# S4V_Motor_Driver_Board_V1_0_Schematic.net
KiCad netlist of a schematic drawn in Altium Designer
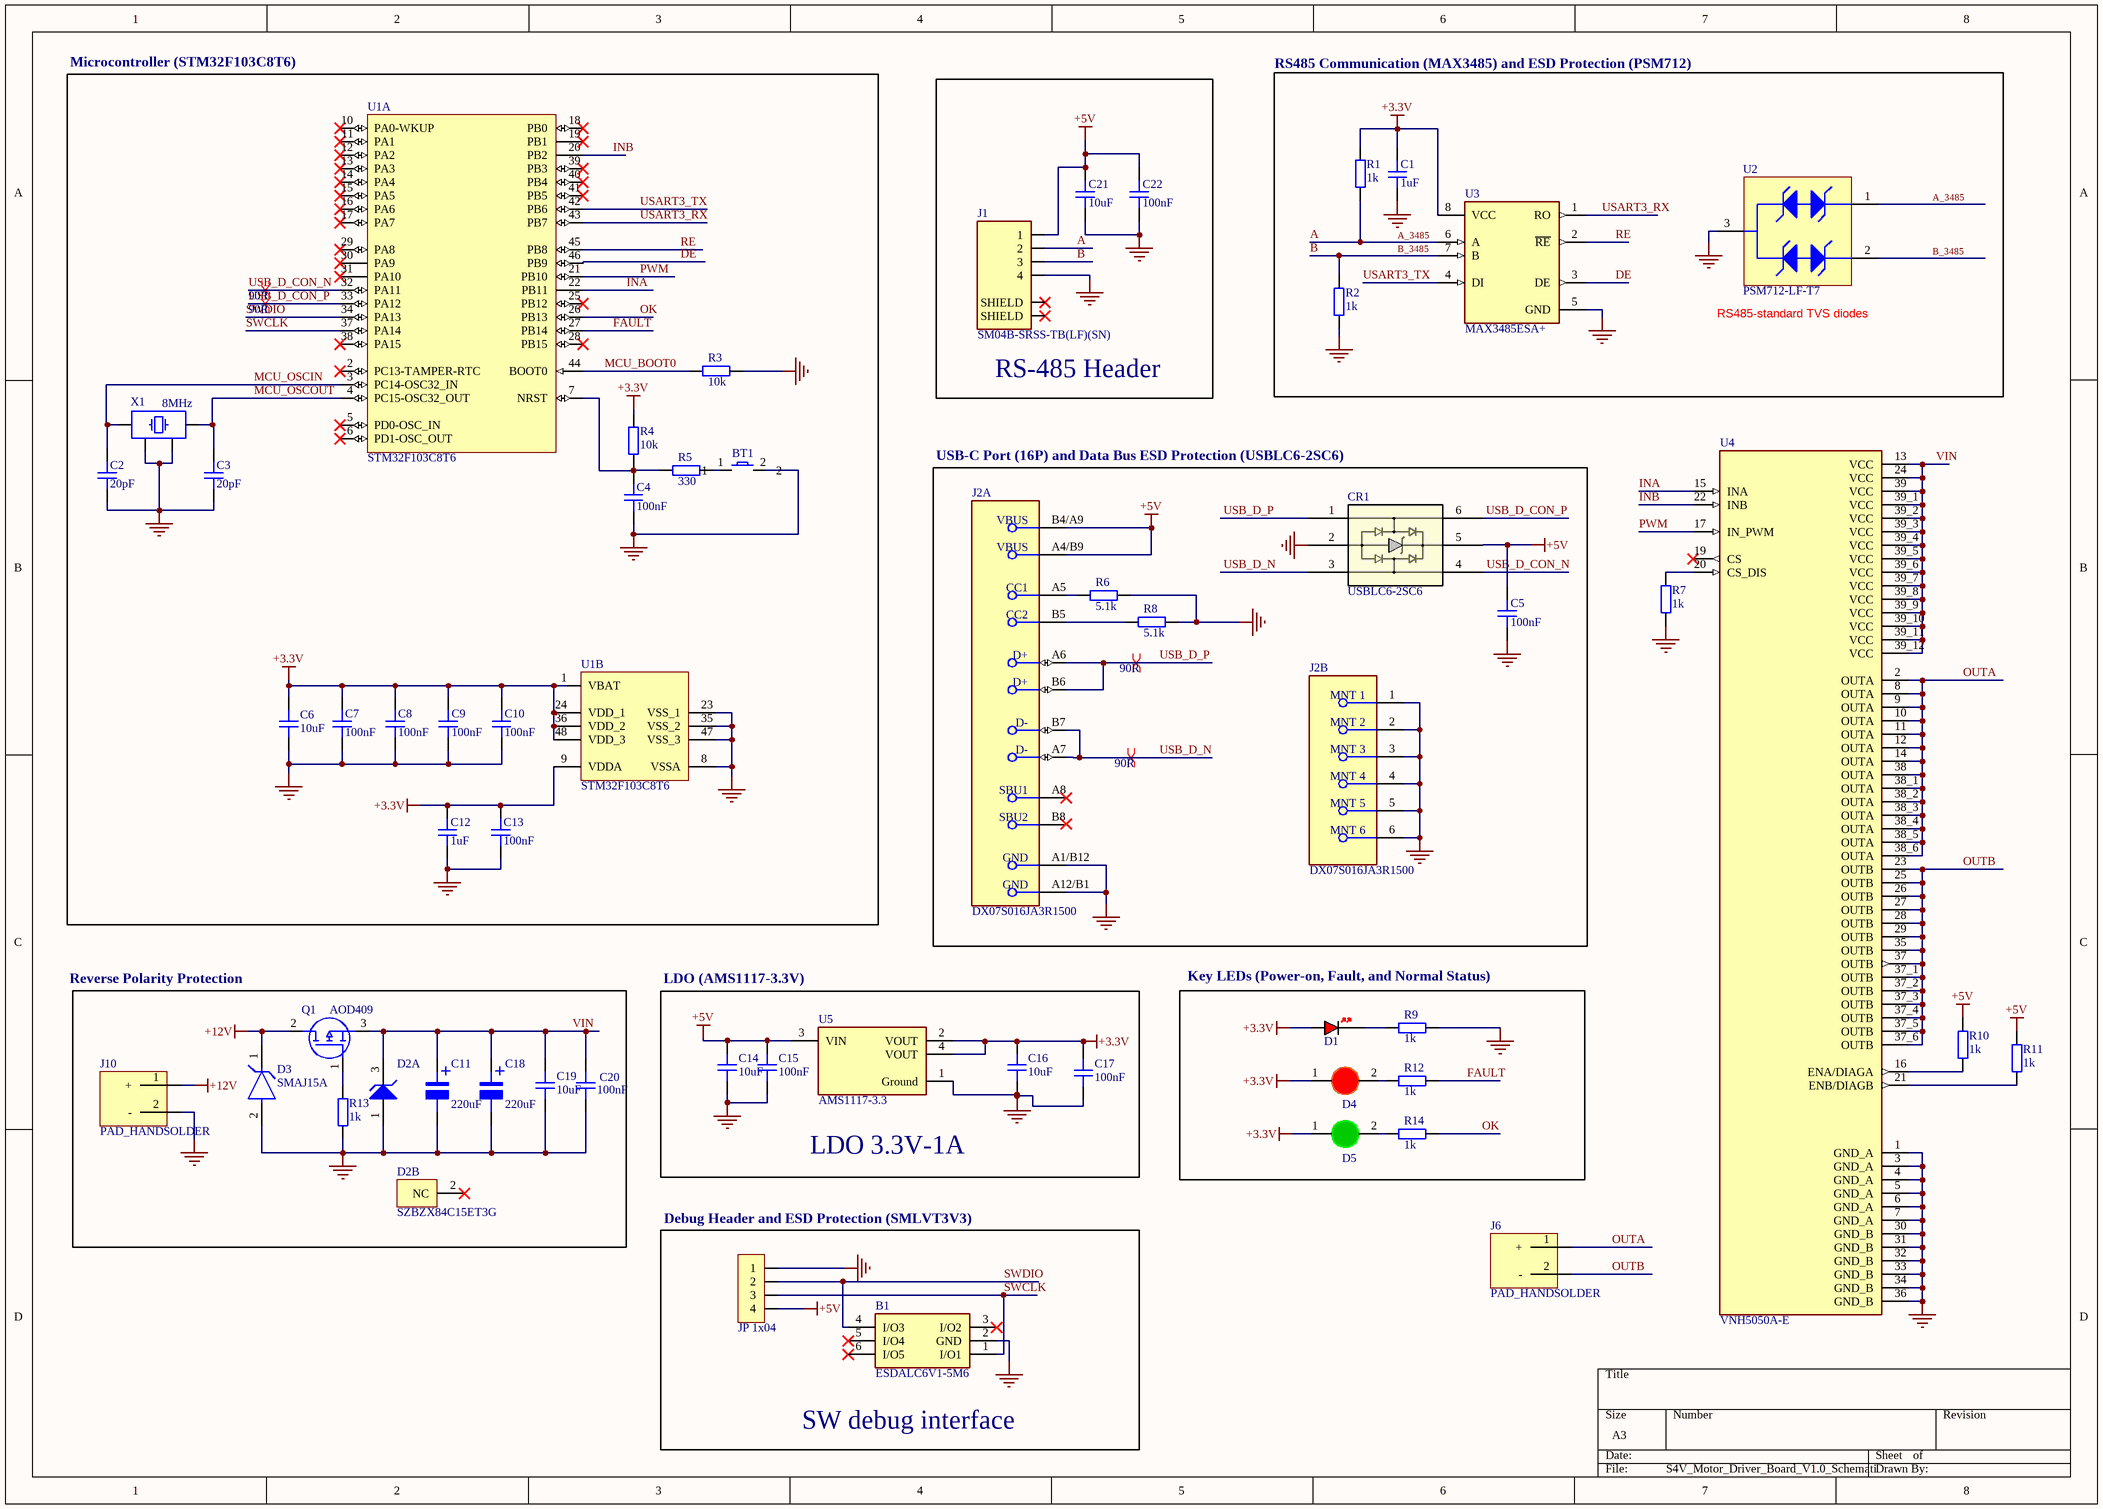
[diagram p0: S4V_Motor_Driver_Board_V1.0_Schematic.SchDoc]

(export (version "E")
  (design (tool "Eeschema 10.0.6"))
  (components
    (comp (ref "B1")
      (value "ESDALC6V1-5M6")
      (footprint "ESDALC6V15M6")
      (description "STMicroelectronics ESDALC6V1-5M6 Quint Uni-Directional TVS Diode, 30W peak, 6-Pin uQFN")
      (fields (field (name "MOUSER PART NUMBER") "511-ESDALC6V1-5M6"))
      (libsource (lib "ESDALC6V1-5M6_new") (part "ESDALC6V1-5M6"))
    )
    (comp (ref "BT1")
      (value "Button_3x4mm_SMD")
      (footprint "SMD_3x4mm_Button_PCBLib:Button_3x4mm_SMD")
      (description "Button SMD 3x4mm 2 Pins")
      (libsource (lib "SMD_3x4mm_Button_SchLib") (part "Button_3x4mm_SMD"))
    )
    (comp (ref "C1")
      (value "1uF")
      (footprint "CAP_0603")
      (description "Capacitor SMD 0603")
      (libsource (lib "Schematic-Lib-PhilsLab") (part "CAP_0603"))
    )
    (comp (ref "C2")
      (value "20pF")
      (footprint "CAP_0603")
      (description "Capacitor SMD 0603")
      (libsource (lib "Schematic-Lib-PhilsLab") (part "CAP_0603"))
    )
    (comp (ref "C3")
      (value "20pF")
      (footprint "CAP_0603")
      (description "Capacitor SMD 0603")
      (libsource (lib "Schematic-Lib-PhilsLab") (part "CAP_0603"))
    )
    (comp (ref "C4")
      (value "100nF")
      (footprint "CAP_0603")
      (description "Capacitor SMD 0603")
      (libsource (lib "Schematic-Lib-PhilsLab") (part "CAP_0603"))
    )
    (comp (ref "C5")
      (value "100nF")
      (footprint "CAP_0603")
      (description "Capacitor SMD 0603")
      (libsource (lib "Schematic-Lib-PhilsLab") (part "CAP_0603"))
    )
    (comp (ref "C6")
      (value "10uF")
      (footprint "CAP_0603")
      (description "Capacitor SMD 0603")
      (libsource (lib "Schematic-Lib-PhilsLab") (part "CAP_0603"))
    )
    (comp (ref "C7")
      (value "100nF")
      (footprint "CAP_0603")
      (description "Capacitor SMD 0603")
      (libsource (lib "Schematic-Lib-PhilsLab") (part "CAP_0603"))
    )
    (comp (ref "C8")
      (value "100nF")
      (footprint "CAP_0603")
      (description "Capacitor SMD 0603")
      (libsource (lib "Schematic-Lib-PhilsLab") (part "CAP_0603"))
    )
    (comp (ref "C9")
      (value "100nF")
      (footprint "CAP_0603")
      (description "Capacitor SMD 0603")
      (libsource (lib "Schematic-Lib-PhilsLab") (part "CAP_0603"))
    )
    (comp (ref "C10")
      (value "100nF")
      (footprint "CAP_0603")
      (description "Capacitor SMD 0603")
      (libsource (lib "Schematic-Lib-PhilsLab") (part "CAP_0603"))
    )
    (comp (ref "C11")
      (value "220uF")
      (footprint "tu nhom 8 (f)")
      (description "Dán")
      (libsource (lib "Altium_Lib_by_KhueNguyenCreator") (part "Tu Nhom 220uF 25V"))
    )
    (comp (ref "C12")
      (value "1uF")
      (footprint "CAP_0603")
      (description "Capacitor SMD 0603")
      (libsource (lib "Schematic-Lib-PhilsLab") (part "CAP_0603"))
    )
    (comp (ref "C13")
      (value "100nF")
      (footprint "CAP_0603")
      (description "Capacitor SMD 0603")
      (libsource (lib "Schematic-Lib-PhilsLab") (part "CAP_0603"))
    )
    (comp (ref "C14")
      (value "10uF")
      (footprint "CAP_0805")
      (description "Capacitor SMD 0805")
      (libsource (lib "Schematic-Lib-PhilsLab") (part "CAP_0805"))
    )
    (comp (ref "C15")
      (value "100nF")
      (footprint "CAP_0805")
      (description "Capacitor SMD 0805")
      (libsource (lib "Schematic-Lib-PhilsLab") (part "CAP_0805"))
    )
    (comp (ref "C16")
      (value "10uF")
      (footprint "CAP_0805")
      (description "Capacitor SMD 0805")
      (libsource (lib "Schematic-Lib-PhilsLab") (part "CAP_0805"))
    )
    (comp (ref "C17")
      (value "100nF")
      (footprint "CAP_0805")
      (description "Capacitor SMD 0805")
      (libsource (lib "Schematic-Lib-PhilsLab") (part "CAP_0805"))
    )
    (comp (ref "C18")
      (value "220uF")
      (footprint "tu nhom 8 (f)")
      (description "Dán")
      (libsource (lib "Altium_Lib_by_KhueNguyenCreator") (part "Tu Nhom 220uF 25V"))
    )
    (comp (ref "C19")
      (value "10uF")
      (footprint "CAP_0805")
      (description "Capacitor SMD 0805")
      (libsource (lib "Schematic-Lib-PhilsLab") (part "CAP_0805"))
    )
    (comp (ref "C20")
      (value "100nF")
      (footprint "CAP_0805")
      (description "Capacitor SMD 0805")
      (libsource (lib "Schematic-Lib-PhilsLab") (part "CAP_0805"))
    )
    (comp (ref "C21")
      (value "10uF")
      (footprint "CAP_0603")
      (description "Capacitor SMD 0603")
      (libsource (lib "Schematic-Lib-PhilsLab") (part "CAP_0603"))
    )
    (comp (ref "C22")
      (value "100nF")
      (footprint "CAP_0603")
      (description "Capacitor SMD 0603")
      (libsource (lib "Schematic-Lib-PhilsLab") (part "CAP_0603"))
    )
    (comp (ref "CR1")
      (value "USBLC6-2SC6")
      (footprint "SOT23-6L_STM")
      (description "ESD Protection for USB 2.0 High Speed")
      (fields (field (name "COPYRIGHT") "Copyright (C) 2025 Ultra Librarian. All rights reserved."))
      (libsource (lib "USBLC6-2SC6") (part "USBLC6-2SC6"))
    )
    (comp (ref "D1")
      (value "RED")
      (footprint "LED_0603_RED")
      (description "LED 0603 RED SMD")
      (libsource (lib "Schematic-Lib-PhilsLab") (part "LED_0603_RED"))
    )
    (comp (ref "D2")
      (value "SZBZX84C15ET3G")
      (footprint "ONSC-SOT-23-3-318-08_V")
      (description "Zener Voltage Regulator, 225 mW, 3-Pin SOT-23, Pb-Free, Tape and Reel")
      (fields (field (name "MANUFACTURER") "On Semiconductor"))
      (libsource (lib "Altium Content Vault") (part "ONSC-A1K3-3"))
    )
    (comp (ref "D3")
      (value "SMAJ15A")
      (footprint "FP-SMA-MFG")
      (description "24.4V Clamp 16.4A Ipp Tvs Diode Surface Mount SMA (DO-214AC)")
      (fields (field (name "OCTOPART") "https://octopart.com/smaj15a-bourns-12809353"))
      (libsource (lib "Altium Content Vault") (part "f813f71cba58e380607f5dd3caf9714"))
    )
    (comp (ref "D4")
      (value "LED 3mm")
      (footprint "LED-3MM-RED")
      (description "Cắm")
      (libsource (lib "Altium_Lib_by_KhueNguyenCreator") (part "LED 3mm Do"))
    )
    (comp (ref "D5")
      (value "LED 3mm")
      (footprint "LED-3MM-GREEN")
      (description "Cắm")
      (libsource (lib "Altium_Lib_by_KhueNguyenCreator") (part "LED 3mm Xanh La"))
    )
    (comp (ref "J1")
      (value "SM04B-SRSS-TB(LF)(SN)")
      (footprint "JST_SM04B-SRSS-TB(LF)(SN)")
      (description "Connector Header Surface Mount, Right Angle 4 position 0.039 (1.00mm)")
      (fields (field (name "MF") "JST Sales"))
      (libsource (lib "SM04B-SRSS-TB_LF__SN_") (part "SM04B-SRSS-TB(LF)(SN)"))
    )
    (comp (ref "J2")
      (value "DX07S016JA3R1500")
      (footprint "FP-DX07S016JA3R1500-MFG")
      (description "CONN RCP USB2.0 TYP C 24P SMD RA")
      (libsource (lib "Altium Content Vault") (part "86c7019cab7ffbad937e454fd6d8a8a"))
    )
    (comp (ref "J6")
      (value "PAD_HANDSOLDER")
      (footprint "PCBComponent_1")
      (description "HandSolder Pad for PWR IN")
      (libsource (lib "HandSolderPadPWR") (part "PAD_HANDSOLDER"))
    )
    (comp (ref "J10")
      (value "PAD_HANDSOLDER")
      (footprint "PCBComponent_1")
      (description "HandSolder Pad for PWR IN")
      (libsource (lib "HandSolderPadPWR") (part "PAD_HANDSOLDER"))
    )
    (comp (ref "JP1")
      (value "JP 1x04")
      (footprint "JP 1x4 DT")
      (description "Cắm")
      (libsource (lib "Altium_Lib_by_KhueNguyenCreator") (part "JP 1x4 2.54 Duc Thang"))
    )
    (comp (ref "Q1")
      (value "AOD409")
      (footprint "AOD409")
      (description "60V P-Channel MOSFET")
      (libsource (lib "AOD409") (part "AOD409"))
    )
    (comp (ref "R1")
      (value "1k")
      (footprint "RES_0603")
      (description "Resistor SMD 0603")
      (libsource (lib "Schematic-Lib-PhilsLab") (part "RES_0603"))
    )
    (comp (ref "R2")
      (value "1k")
      (footprint "RES_0603")
      (description "Resistor SMD 0603")
      (libsource (lib "Schematic-Lib-PhilsLab") (part "RES_0603"))
    )
    (comp (ref "R3")
      (value "10k")
      (footprint "RES_0603")
      (description "Resistor SMD 0603")
      (libsource (lib "Schematic-Lib-PhilsLab") (part "RES_0603"))
    )
    (comp (ref "R4")
      (value "10k")
      (footprint "RES_0603")
      (description "Resistor SMD 0603")
      (libsource (lib "Schematic-Lib-PhilsLab") (part "RES_0603"))
    )
    (comp (ref "R5")
      (value "330")
      (footprint "RES_0603")
      (description "Resistor SMD 0603")
      (libsource (lib "Schematic-Lib-PhilsLab") (part "RES_0603"))
    )
    (comp (ref "R6")
      (value "5.1k")
      (footprint "RES_0603")
      (description "Resistor SMD 0603")
      (libsource (lib "Schematic-Lib-PhilsLab") (part "RES_0603"))
    )
    (comp (ref "R7")
      (value "1k")
      (footprint "RES_0402")
      (description "Resistor SMD 0402")
      (libsource (lib "Schematic-Lib-PhilsLab") (part "RES_0402"))
    )
    (comp (ref "R8")
      (value "5.1k")
      (footprint "RES_0603")
      (description "Resistor SMD 0603")
      (libsource (lib "Schematic-Lib-PhilsLab") (part "RES_0603"))
    )
    (comp (ref "R9")
      (value "1k")
      (footprint "RES_0603")
      (description "Resistor SMD 0603")
      (libsource (lib "Schematic-Lib-PhilsLab") (part "RES_0603"))
    )
    (comp (ref "R10")
      (value "1k")
      (footprint "RES_0402")
      (description "Resistor SMD 0402")
      (libsource (lib "Schematic-Lib-PhilsLab") (part "RES_0402"))
    )
    (comp (ref "R11")
      (value "1k")
      (footprint "RES_0402")
      (description "Resistor SMD 0402")
      (libsource (lib "Schematic-Lib-PhilsLab") (part "RES_0402"))
    )
    (comp (ref "R12")
      (value "1k")
      (footprint "RES_0603")
      (description "Resistor SMD 0603")
      (libsource (lib "Schematic-Lib-PhilsLab") (part "RES_0603"))
    )
    (comp (ref "R13")
      (value "1k")
      (footprint "RES_0603")
      (description "Resistor SMD 0603")
      (libsource (lib "Schematic-Lib-PhilsLab") (part "RES_0603"))
    )
    (comp (ref "R14")
      (value "1k")
      (footprint "RES_0603")
      (description "Resistor SMD 0603")
      (libsource (lib "Schematic-Lib-PhilsLab") (part "RES_0603"))
    )
    (comp (ref "U1")
      (value "STM32F103C8T6")
      (footprint "STM-LQFP48_L")
      (libsource (lib "Altium Content Vault") (part "MC-ARM-STM32F103X8_B-SQ48"))
    )
    (comp (ref "U2")
      (value "PSM712-LF-T7")
      (footprint "PRKT-SOT23-3_V")
      (fields (field (name "MANUFACTURER") "Protek Devices") (field (name "VOLTAGE") "12V"))
      (libsource (lib "Altium Content Vault") (part "PRTK-PSM712-SOT23-3"))
    )
    (comp (ref "U3")
      (value "MAX3485ESA+")
      (footprint "FP-S8-5-MFG")
      (description "IC TXRX RS485/422 10MBPS 8SOIC")
      (fields
        (field (name "MANUFACTURER PART NUMBER") "MAX3485EESA+")
        (field (name "OCTOPART") "https://octopart.com/max3485eesa%2B-maxim+integrated-39731903")
      )
      (libsource (lib "Altium Content Vault") (part "be0caabdb159a9a12bcb36ec340889e"))
    )
    (comp (ref "U4")
      (value "VNH5050A-E")
      (footprint "SOP50P1030X247-39N")
      (description "- Motor Driver Power MOSFET Parallel, PWM PowerSSO-36 TP")
      (fields (field (name "MF") "STMicroelectronics"))
      (libsource (lib "VNH5050A-E") (part "VNH5050A-E"))
    )
    (comp (ref "U5")
      (value "AMS1117-3.3")
      (footprint "FP-AMS1117-IPC_C")
      (description "LDO Voltage Regulators 1A, 3.3V")
      (fields
        (field (name "OCTOPART") "https://octopart.com/ams1117-3.3-advanced+monolithic+systems-25899300")
        (field (name "MANUFACTURER") "Advanced Monolithic Systems")
      )
      (libsource (lib "Altium Content Vault") (part "8bdbb5f8e77002000e30dd2845d0354"))
    )
    (comp (ref "X1")
      (value "8MHz")
      (footprint "XTAL_3225")
      (description "Crystal SMD 24MHz 10PPM 7pF 3225")
      (fields
        (field (name "MANUFACTURER") "Epson")
        (field (name "MANUFACTURER PART NUMBER") "TSX-3225 24.0000MF15X-AC")
      )
      (libsource (lib "Schematic-Lib-PhilsLab") (part "TSX-3225_24.0000MF15X-AC"))
    )
  )
  (nets
    (net (code "1") (name "+3.3V") (class "Default")
      (node (ref "C1") (pin "2") (pinfunction "2_2") (pintype "passive"))
      (node (ref "C10") (pin "2") (pinfunction "2_2") (pintype "passive"))
      (node (ref "C12") (pin "2") (pinfunction "2_2") (pintype "passive"))
      (node (ref "C13") (pin "2") (pinfunction "2_2") (pintype "passive"))
      (node (ref "C16") (pin "2") (pinfunction "2_2") (pintype "passive"))
      (node (ref "C17") (pin "2") (pinfunction "2_2") (pintype "passive"))
      (node (ref "C6") (pin "2") (pinfunction "2_2") (pintype "passive"))
      (node (ref "C7") (pin "2") (pinfunction "2_2") (pintype "passive"))
      (node (ref "C8") (pin "2") (pinfunction "2_2") (pintype "passive"))
      (node (ref "C9") (pin "2") (pinfunction "2_2") (pintype "passive"))
      (node (ref "D1") (pin "A") (pinfunction "A_A") (pintype "passive"))
      (node (ref "D4") (pin "1") (pinfunction "A_1") (pintype "passive"))
      (node (ref "D5") (pin "1") (pinfunction "A_1") (pintype "passive"))
      (node (ref "R1") (pin "1") (pinfunction "1_1") (pintype "passive"))
      (node (ref "R4") (pin "2") (pinfunction "2_2") (pintype "passive"))
      (node (ref "U1") (pin "1") (pinfunction "VBAT_1") (pintype "power_in"))
      (node (ref "U1") (pin "24") (pinfunction "VDD_1_24") (pintype "power_in"))
      (node (ref "U1") (pin "36") (pinfunction "VDD_2_36") (pintype "power_in"))
      (node (ref "U1") (pin "48") (pinfunction "VDD_3_48") (pintype "power_in"))
      (node (ref "U1") (pin "9") (pinfunction "VDDA_9") (pintype "power_in"))
      (node (ref "U3") (pin "8") (pinfunction "VCC_8") (pintype "power_in"))
      (node (ref "U5") (pin "2") (pinfunction "VOUT_2") (pintype "passive"))
      (node (ref "U5") (pin "4") (pinfunction "VOUT_4") (pintype "passive"))
    )
    (net (code "2") (name "+5V") (class "Default")
      (node (ref "C14") (pin "2") (pinfunction "2_2") (pintype "passive"))
      (node (ref "C15") (pin "2") (pinfunction "2_2") (pintype "passive"))
      (node (ref "C21") (pin "2") (pinfunction "2_2") (pintype "passive"))
      (node (ref "C22") (pin "2") (pinfunction "2_2") (pintype "passive"))
      (node (ref "C5") (pin "2") (pinfunction "2_2") (pintype "passive"))
      (node (ref "CR1") (pin "5") (pinfunction "5_5") (pintype "passive"))
      (node (ref "J1") (pin "1") (pinfunction "1_1") (pintype "passive"))
      (node (ref "J2") (pin "A4/B9") (pinfunction "VBUS_A4/B9") (pintype "power_in"))
      (node (ref "J2") (pin "B4/A9") (pinfunction "VBUS_B4/A9") (pintype "power_in"))
      (node (ref "JP1") (pin "4") (pinfunction "4_4") (pintype "passive"))
      (node (ref "R10") (pin "2") (pinfunction "2_2") (pintype "passive"))
      (node (ref "R11") (pin "2") (pinfunction "2_2") (pintype "passive"))
      (node (ref "U5") (pin "3") (pinfunction "VIN_3") (pintype "power_in"))
    )
    (net (code "3") (name "+12V") (class "Default")
      (node (ref "D3") (pin "1") (pinfunction "C_1") (pintype "passive"))
      (node (ref "J10") (pin "1") (pinfunction "+_1") (pintype "passive"))
      (node (ref "Q1") (pin "2") (pinfunction "D_2") (pintype "passive"))
    )
    (net (code "4") (name "/A") (class "Default")
      (node (ref "J1") (pin "2") (pinfunction "2_2") (pintype "passive"))
      (node (ref "R1") (pin "2") (pinfunction "2_2") (pintype "passive"))
      (node (ref "U2") (pin "1") (pinfunction "1_1") (pintype "passive"))
      (node (ref "U3") (pin "6") (pinfunction "A_6") (pintype "input"))
    )
    (net (code "5") (name "/B") (class "Default")
      (node (ref "J1") (pin "3") (pinfunction "3_3") (pintype "passive"))
      (node (ref "R2") (pin "2") (pinfunction "2_2") (pintype "passive"))
      (node (ref "U2") (pin "2") (pinfunction "2_2") (pintype "passive"))
      (node (ref "U3") (pin "7") (pinfunction "B_7") (pintype "input"))
    )
    (net (code "6") (name "/DE") (class "Default")
      (node (ref "U1") (pin "46") (pinfunction "PB9_46") (pintype "bidirectional"))
      (node (ref "U3") (pin "3") (pinfunction "DE_3") (pintype "output"))
    )
    (net (code "7") (name "/FAULT") (class "Default")
      (node (ref "R12") (pin "2") (pinfunction "2_2") (pintype "passive"))
      (node (ref "U1") (pin "27") (pinfunction "PB14_27") (pintype "bidirectional"))
    )
    (net (code "8") (name "/INA") (class "Default")
      (node (ref "U1") (pin "22") (pinfunction "PB11_22") (pintype "passive"))
      (node (ref "U4") (pin "15") (pinfunction "INA_15") (pintype "input"))
    )
    (net (code "9") (name "/INB") (class "Default")
      (node (ref "U1") (pin "20") (pinfunction "PB2_20") (pintype "passive"))
      (node (ref "U4") (pin "22") (pinfunction "INB_22") (pintype "input"))
    )
    (net (code "10") (name "/MCU_BOOT0") (class "Default")
      (node (ref "R3") (pin "1") (pinfunction "1_1") (pintype "passive"))
      (node (ref "U1") (pin "44") (pinfunction "BOOT0_44") (pintype "input"))
    )
    (net (code "11") (name "/MCU_OSCIN") (class "Default")
      (node (ref "C2") (pin "2") (pinfunction "2_2") (pintype "passive"))
      (node (ref "U1") (pin "3") (pinfunction "PC14-OSC32_IN_3") (pintype "bidirectional"))
      (node (ref "X1") (pin "1") (pinfunction "1_1") (pintype "passive"))
    )
    (net (code "12") (name "/MCU_OSCOUT") (class "Default")
      (node (ref "C3") (pin "2") (pinfunction "2_2") (pintype "passive"))
      (node (ref "U1") (pin "4") (pinfunction "PC15-OSC32_OUT_4") (pintype "bidirectional"))
      (node (ref "X1") (pin "3") (pinfunction "3_3") (pintype "passive"))
    )
    (net (code "13") (name "/OK") (class "Default")
      (node (ref "R14") (pin "2") (pinfunction "2_2") (pintype "passive"))
      (node (ref "U1") (pin "26") (pinfunction "PB13_26") (pintype "bidirectional"))
    )
    (net (code "14") (name "/OUTA") (class "Default")
      (node (ref "J6") (pin "1") (pinfunction "+_1") (pintype "passive"))
      (node (ref "U4") (pin "10") (pinfunction "OUTA_10") (pintype "passive"))
      (node (ref "U4") (pin "11") (pinfunction "OUTA_11") (pintype "passive"))
      (node (ref "U4") (pin "12") (pinfunction "OUTA_12") (pintype "passive"))
      (node (ref "U4") (pin "14") (pinfunction "OUTA_14") (pintype "passive"))
      (node (ref "U4") (pin "2") (pinfunction "OUTA_2") (pintype "passive"))
      (node (ref "U4") (pin "38") (pinfunction "OUTA_38") (pintype "passive"))
      (node (ref "U4") (pin "38_1") (pinfunction "OUTA_38_1") (pintype "passive"))
      (node (ref "U4") (pin "38_2") (pinfunction "OUTA_38_2") (pintype "passive"))
      (node (ref "U4") (pin "38_3") (pinfunction "OUTA_38_3") (pintype "passive"))
      (node (ref "U4") (pin "38_4") (pinfunction "OUTA_38_4") (pintype "passive"))
      (node (ref "U4") (pin "38_5") (pinfunction "OUTA_38_5") (pintype "passive"))
      (node (ref "U4") (pin "38_6") (pinfunction "OUTA_38_6") (pintype "passive"))
      (node (ref "U4") (pin "8") (pinfunction "OUTA_8") (pintype "passive"))
      (node (ref "U4") (pin "9") (pinfunction "OUTA_9") (pintype "passive"))
    )
    (net (code "15") (name "/OUTB") (class "Default")
      (node (ref "J6") (pin "2") (pinfunction "-_2") (pintype "passive"))
      (node (ref "U4") (pin "23") (pinfunction "OUTB_23") (pintype "passive"))
      (node (ref "U4") (pin "25") (pinfunction "OUTB_25") (pintype "passive"))
      (node (ref "U4") (pin "26") (pinfunction "OUTB_26") (pintype "passive"))
      (node (ref "U4") (pin "27") (pinfunction "OUTB_27") (pintype "passive"))
      (node (ref "U4") (pin "28") (pinfunction "OUTB_28") (pintype "passive"))
      (node (ref "U4") (pin "29") (pinfunction "OUTB_29") (pintype "passive"))
      (node (ref "U4") (pin "35") (pinfunction "OUTB_35") (pintype "passive"))
      (node (ref "U4") (pin "37") (pinfunction "OUTB_37") (pintype "output"))
      (node (ref "U4") (pin "37_1") (pinfunction "OUTB_37_1") (pintype "passive"))
      (node (ref "U4") (pin "37_2") (pinfunction "OUTB_37_2") (pintype "passive"))
      (node (ref "U4") (pin "37_3") (pinfunction "OUTB_37_3") (pintype "passive"))
      (node (ref "U4") (pin "37_4") (pinfunction "OUTB_37_4") (pintype "passive"))
      (node (ref "U4") (pin "37_5") (pinfunction "OUTB_37_5") (pintype "passive"))
      (node (ref "U4") (pin "37_6") (pinfunction "OUTB_37_6") (pintype "passive"))
    )
    (net (code "16") (name "/PWM") (class "Default")
      (node (ref "U1") (pin "21") (pinfunction "PB10_21") (pintype "bidirectional"))
      (node (ref "U4") (pin "17") (pinfunction "IN_PWM_17") (pintype "input"))
    )
    (net (code "17") (name "/RE") (class "Default")
      (node (ref "U1") (pin "45") (pinfunction "PB8_45") (pintype "bidirectional"))
      (node (ref "U3") (pin "2") (pinfunction "~{RE}_2") (pintype "output"))
    )
    (net (code "18") (name "/SWCLK") (class "Default")
      (node (ref "B1") (pin "1") (pinfunction "I/O1_1") (pintype "passive"))
      (node (ref "JP1") (pin "3") (pinfunction "3_3") (pintype "passive"))
      (node (ref "U1") (pin "37") (pinfunction "PA14_37") (pintype "bidirectional"))
    )
    (net (code "19") (name "/SWDIO") (class "Default")
      (node (ref "B1") (pin "4") (pinfunction "I/O3_4") (pintype "passive"))
      (node (ref "JP1") (pin "2") (pinfunction "2_2") (pintype "passive"))
      (node (ref "U1") (pin "34") (pinfunction "PA13_34") (pintype "bidirectional"))
    )
    (net (code "20") (name "/USART3_RX") (class "Default")
      (node (ref "U1") (pin "43") (pinfunction "PB7_43") (pintype "bidirectional"))
      (node (ref "U3") (pin "1") (pinfunction "RO_1") (pintype "output"))
    )
    (net (code "21") (name "/USART3_TX") (class "Default")
      (node (ref "U1") (pin "42") (pinfunction "PB6_42") (pintype "bidirectional"))
      (node (ref "U3") (pin "4") (pinfunction "DI_4") (pintype "input"))
    )
    (net (code "22") (name "/USB_D_CON_N") (class "Default")
      (node (ref "CR1") (pin "4") (pinfunction "4_4") (pintype "passive"))
      (node (ref "U1") (pin "32") (pinfunction "PA11_32") (pintype "bidirectional"))
    )
    (net (code "23") (name "/USB_D_CON_P") (class "Default")
      (node (ref "CR1") (pin "6") (pinfunction "6_6") (pintype "passive"))
      (node (ref "U1") (pin "33") (pinfunction "PA12_33") (pintype "bidirectional"))
    )
    (net (code "24") (name "/USB_D_N") (class "Default")
      (node (ref "CR1") (pin "3") (pinfunction "3_3") (pintype "passive"))
      (node (ref "J2") (pin "A7") (pinfunction "D-_A7") (pintype "bidirectional"))
      (node (ref "J2") (pin "B7") (pinfunction "D-_B7") (pintype "bidirectional"))
    )
    (net (code "25") (name "/USB_D_P") (class "Default")
      (node (ref "CR1") (pin "1") (pinfunction "1_1") (pintype "passive"))
      (node (ref "J2") (pin "A6") (pinfunction "D+_A6") (pintype "bidirectional"))
      (node (ref "J2") (pin "B6") (pinfunction "D+_B6") (pintype "bidirectional"))
    )
    (net (code "26") (name "/VIN") (class "Default")
      (node (ref "C11") (pin "1") (pinfunction "1_1") (pintype "passive"))
      (node (ref "C18") (pin "1") (pinfunction "1_1") (pintype "passive"))
      (node (ref "C19") (pin "2") (pinfunction "2_2") (pintype "passive"))
      (node (ref "C20") (pin "2") (pinfunction "2_2") (pintype "passive"))
      (node (ref "D2") (pin "3") (pinfunction "K_3") (pintype "passive"))
      (node (ref "Q1") (pin "3") (pinfunction "S_3") (pintype "passive"))
      (node (ref "U4") (pin "13") (pinfunction "VCC_13") (pintype "power_in"))
      (node (ref "U4") (pin "24") (pinfunction "VCC_24") (pintype "power_in"))
      (node (ref "U4") (pin "39") (pinfunction "VCC_39") (pintype "power_in"))
      (node (ref "U4") (pin "39_1") (pinfunction "VCC_39_1") (pintype "power_in"))
      (node (ref "U4") (pin "39_10") (pinfunction "VCC_39_10") (pintype "power_in"))
      (node (ref "U4") (pin "39_11") (pinfunction "VCC_39_11") (pintype "power_in"))
      (node (ref "U4") (pin "39_12") (pinfunction "VCC_39_12") (pintype "power_in"))
      (node (ref "U4") (pin "39_2") (pinfunction "VCC_39_2") (pintype "power_in"))
      (node (ref "U4") (pin "39_3") (pinfunction "VCC_39_3") (pintype "power_in"))
      (node (ref "U4") (pin "39_4") (pinfunction "VCC_39_4") (pintype "power_in"))
      (node (ref "U4") (pin "39_5") (pinfunction "VCC_39_5") (pintype "power_in"))
      (node (ref "U4") (pin "39_6") (pinfunction "VCC_39_6") (pintype "power_in"))
      (node (ref "U4") (pin "39_7") (pinfunction "VCC_39_7") (pintype "power_in"))
      (node (ref "U4") (pin "39_8") (pinfunction "VCC_39_8") (pintype "power_in"))
      (node (ref "U4") (pin "39_9") (pinfunction "VCC_39_9") (pintype "power_in"))
    )
    (net (code "27") (name "GND") (class "Default")
      (node (ref "B1") (pin "2") (pinfunction "GND_2") (pintype "passive"))
      (node (ref "BT1") (pin "2") (pinfunction "2_2") (pintype "passive"))
      (node (ref "C1") (pin "1") (pinfunction "1_1") (pintype "passive"))
      (node (ref "C10") (pin "1") (pinfunction "1_1") (pintype "passive"))
      (node (ref "C11") (pin "2") (pinfunction "2_2") (pintype "passive"))
      (node (ref "C12") (pin "1") (pinfunction "1_1") (pintype "passive"))
      (node (ref "C13") (pin "1") (pinfunction "1_1") (pintype "passive"))
      (node (ref "C14") (pin "1") (pinfunction "1_1") (pintype "passive"))
      (node (ref "C15") (pin "1") (pinfunction "1_1") (pintype "passive"))
      (node (ref "C16") (pin "1") (pinfunction "1_1") (pintype "passive"))
      (node (ref "C17") (pin "1") (pinfunction "1_1") (pintype "passive"))
      (node (ref "C18") (pin "2") (pinfunction "2_2") (pintype "passive"))
      (node (ref "C19") (pin "1") (pinfunction "1_1") (pintype "passive"))
      (node (ref "C2") (pin "1") (pinfunction "1_1") (pintype "passive"))
      (node (ref "C20") (pin "1") (pinfunction "1_1") (pintype "passive"))
      (node (ref "C21") (pin "1") (pinfunction "1_1") (pintype "passive"))
      (node (ref "C22") (pin "1") (pinfunction "1_1") (pintype "passive"))
      (node (ref "C3") (pin "1") (pinfunction "1_1") (pintype "passive"))
      (node (ref "C4") (pin "1") (pinfunction "1_1") (pintype "passive"))
      (node (ref "C5") (pin "1") (pinfunction "1_1") (pintype "passive"))
      (node (ref "C6") (pin "1") (pinfunction "1_1") (pintype "passive"))
      (node (ref "C7") (pin "1") (pinfunction "1_1") (pintype "passive"))
      (node (ref "C8") (pin "1") (pinfunction "1_1") (pintype "passive"))
      (node (ref "C9") (pin "1") (pinfunction "1_1") (pintype "passive"))
      (node (ref "CR1") (pin "2") (pinfunction "2_2") (pintype "passive"))
      (node (ref "D2") (pin "1") (pinfunction "A_1") (pintype "passive"))
      (node (ref "D3") (pin "2") (pinfunction "A_2") (pintype "passive"))
      (node (ref "J1") (pin "4") (pinfunction "4_4") (pintype "passive"))
      (node (ref "J10") (pin "2") (pinfunction "-_2") (pintype "passive"))
      (node (ref "J2") (pin "1") (pinfunction "MNT_1_1") (pintype "passive"))
      (node (ref "J2") (pin "2") (pinfunction "MNT_2_2") (pintype "passive"))
      (node (ref "J2") (pin "3") (pinfunction "MNT_3_3") (pintype "passive"))
      (node (ref "J2") (pin "4") (pinfunction "MNT_4_4") (pintype "passive"))
      (node (ref "J2") (pin "5") (pinfunction "MNT_5_5") (pintype "passive"))
      (node (ref "J2") (pin "6") (pinfunction "MNT_6_6") (pintype "passive"))
      (node (ref "J2") (pin "A1/B12") (pinfunction "GND_A1/B12") (pintype "power_in"))
      (node (ref "J2") (pin "A12/B1") (pinfunction "GND_A12/B1") (pintype "power_in"))
      (node (ref "JP1") (pin "1") (pinfunction "1_1") (pintype "passive"))
      (node (ref "R13") (pin "1") (pinfunction "1_1") (pintype "passive"))
      (node (ref "R2") (pin "1") (pinfunction "1_1") (pintype "passive"))
      (node (ref "R3") (pin "2") (pinfunction "2_2") (pintype "passive"))
      (node (ref "R6") (pin "2") (pinfunction "2_2") (pintype "passive"))
      (node (ref "R7") (pin "1") (pinfunction "1_1") (pintype "passive"))
      (node (ref "R8") (pin "2") (pinfunction "2_2") (pintype "passive"))
      (node (ref "R9") (pin "2") (pinfunction "2_2") (pintype "passive"))
      (node (ref "U1") (pin "23") (pinfunction "VSS_1_23") (pintype "power_in"))
      (node (ref "U1") (pin "35") (pinfunction "VSS_2_35") (pintype "power_in"))
      (node (ref "U1") (pin "47") (pinfunction "VSS_3_47") (pintype "power_in"))
      (node (ref "U1") (pin "8") (pinfunction "VSSA_8") (pintype "power_in"))
      (node (ref "U2") (pin "3") (pinfunction "3_3") (pintype "passive"))
      (node (ref "U3") (pin "5") (pinfunction "GND_5") (pintype "power_in"))
      (node (ref "U4") (pin "1") (pinfunction "GND_A_1") (pintype "power_in"))
      (node (ref "U4") (pin "3") (pinfunction "GND_A_3") (pintype "power_in"))
      (node (ref "U4") (pin "30") (pinfunction "GND_B_30") (pintype "power_in"))
      (node (ref "U4") (pin "31") (pinfunction "GND_B_31") (pintype "power_in"))
      (node (ref "U4") (pin "32") (pinfunction "GND_B_32") (pintype "power_in"))
      (node (ref "U4") (pin "33") (pinfunction "GND_B_33") (pintype "power_in"))
      (node (ref "U4") (pin "34") (pinfunction "GND_B_34") (pintype "power_in"))
      (node (ref "U4") (pin "36") (pinfunction "GND_B_36") (pintype "power_in"))
      (node (ref "U4") (pin "4") (pinfunction "GND_A_4") (pintype "power_in"))
      (node (ref "U4") (pin "5") (pinfunction "GND_A_5") (pintype "power_in"))
      (node (ref "U4") (pin "6") (pinfunction "GND_A_6") (pintype "power_in"))
      (node (ref "U4") (pin "7") (pinfunction "GND_A_7") (pintype "power_in"))
      (node (ref "U5") (pin "1") (pinfunction "Ground_1") (pintype "power_in"))
      (node (ref "X1") (pin "2") (pinfunction "2_2") (pintype "passive"))
      (node (ref "X1") (pin "4") (pinfunction "4_4") (pintype "passive"))
    )
    (net (code "28") (name "Net-(BT1-Pad1)") (class "Default")
      (node (ref "BT1") (pin "1") (pinfunction "1_1") (pintype "passive"))
      (node (ref "R5") (pin "2") (pinfunction "2_2") (pintype "passive"))
    )
    (net (code "29") (name "Net-(D1-PadK)") (class "Default")
      (node (ref "D1") (pin "K") (pinfunction "K_K") (pintype "passive"))
      (node (ref "R9") (pin "1") (pinfunction "1_1") (pintype "passive"))
    )
    (net (code "30") (name "Net-(D4-K)") (class "Default")
      (node (ref "D4") (pin "2") (pinfunction "K_2") (pintype "passive"))
      (node (ref "R12") (pin "1") (pinfunction "1_1") (pintype "passive"))
    )
    (net (code "31") (name "Net-(D5-K)") (class "Default")
      (node (ref "D5") (pin "2") (pinfunction "K_2") (pintype "passive"))
      (node (ref "R14") (pin "1") (pinfunction "1_1") (pintype "passive"))
    )
    (net (code "32") (name "Net-(J2A-CC1)") (class "Default")
      (node (ref "J2") (pin "A5") (pinfunction "CC1_A5") (pintype "passive"))
      (node (ref "R6") (pin "1") (pinfunction "1_1") (pintype "passive"))
    )
    (net (code "33") (name "Net-(J2A-CC2)") (class "Default")
      (node (ref "J2") (pin "B5") (pinfunction "CC2_B5") (pintype "passive"))
      (node (ref "R8") (pin "1") (pinfunction "1_1") (pintype "passive"))
    )
    (net (code "34") (name "Net-(Q1-G)") (class "Default")
      (node (ref "Q1") (pin "1") (pinfunction "G_1") (pintype "passive"))
      (node (ref "R13") (pin "2") (pinfunction "2_2") (pintype "passive"))
    )
    (net (code "35") (name "Net-(U1A-NRST)") (class "Default")
      (node (ref "C4") (pin "2") (pinfunction "2_2") (pintype "passive"))
      (node (ref "R4") (pin "1") (pinfunction "1_1") (pintype "passive"))
      (node (ref "R5") (pin "1") (pinfunction "1_1") (pintype "passive"))
      (node (ref "U1") (pin "7") (pinfunction "NRST_7") (pintype "bidirectional"))
    )
    (net (code "36") (name "Net-(U4-CS_DIS)") (class "Default")
      (node (ref "R7") (pin "2") (pinfunction "2_2") (pintype "passive"))
      (node (ref "U4") (pin "20") (pinfunction "CS_DIS_20") (pintype "input"))
    )
    (net (code "37") (name "Net-(U4-ENA{slash}DIAGA)") (class "Default")
      (node (ref "R10") (pin "1") (pinfunction "1_1") (pintype "passive"))
      (node (ref "U4") (pin "16") (pinfunction "ENA/DIAGA_16") (pintype "output"))
    )
    (net (code "38") (name "Net-(U4-ENB{slash}DIAGB)") (class "Default")
      (node (ref "R11") (pin "1") (pinfunction "1_1") (pintype "passive"))
      (node (ref "U4") (pin "21") (pinfunction "ENB/DIAGB_21") (pintype "output"))
    )
    (net (code "39") (name "unconnected-(B1-I{slash}O2-Pad3)") (class "Default")
      (node (ref "B1") (pin "3") (pinfunction "I/O2_3") (pintype "passive+no_connect"))
    )
    (net (code "40") (name "unconnected-(B1-I{slash}O4-Pad5)") (class "Default")
      (node (ref "B1") (pin "5") (pinfunction "I/O4_5") (pintype "passive+no_connect"))
    )
    (net (code "41") (name "unconnected-(B1-I{slash}O5-Pad6)") (class "Default")
      (node (ref "B1") (pin "6") (pinfunction "I/O5_6") (pintype "passive+no_connect"))
    )
    (net (code "42") (name "unconnected-(D2B-NC-Pad2)") (class "Default")
      (node (ref "D2") (pin "2") (pinfunction "NC_2") (pintype "passive+no_connect"))
    )
    (net (code "43") (name "unconnected-(J1-SHIELD-PadS1)") (class "Default")
      (node (ref "J1") (pin "S1") (pinfunction "SHIELD_S1") (pintype "passive+no_connect"))
    )
    (net (code "44") (name "unconnected-(J1-SHIELD-PadS2)") (class "Default")
      (node (ref "J1") (pin "S2") (pinfunction "SHIELD_S2") (pintype "passive+no_connect"))
    )
    (net (code "45") (name "unconnected-(J2A-SBU1-PadA8)") (class "Default")
      (node (ref "J2") (pin "A8") (pinfunction "SBU1_A8") (pintype "passive+no_connect"))
    )
    (net (code "46") (name "unconnected-(J2A-SBU2-PadB8)") (class "Default")
      (node (ref "J2") (pin "B8") (pinfunction "SBU2_B8") (pintype "passive"))
    )
    (net (code "47") (name "unconnected-(U1A-PA0-WKUP-Pad10)") (class "Default")
      (node (ref "U1") (pin "10") (pinfunction "PA0-WKUP_10") (pintype "bidirectional+no_connect"))
    )
    (net (code "48") (name "unconnected-(U1A-PA1-Pad11)") (class "Default")
      (node (ref "U1") (pin "11") (pinfunction "PA1_11") (pintype "bidirectional+no_connect"))
    )
    (net (code "49") (name "unconnected-(U1A-PA2-Pad12)") (class "Default")
      (node (ref "U1") (pin "12") (pinfunction "PA2_12") (pintype "bidirectional+no_connect"))
    )
    (net (code "50") (name "unconnected-(U1A-PA3-Pad13)") (class "Default")
      (node (ref "U1") (pin "13") (pinfunction "PA3_13") (pintype "bidirectional+no_connect"))
    )
    (net (code "51") (name "unconnected-(U1A-PA4-Pad14)") (class "Default")
      (node (ref "U1") (pin "14") (pinfunction "PA4_14") (pintype "bidirectional+no_connect"))
    )
    (net (code "52") (name "unconnected-(U1A-PA5-Pad15)") (class "Default")
      (node (ref "U1") (pin "15") (pinfunction "PA5_15") (pintype "bidirectional+no_connect"))
    )
    (net (code "53") (name "unconnected-(U1A-PA6-Pad16)") (class "Default")
      (node (ref "U1") (pin "16") (pinfunction "PA6_16") (pintype "bidirectional+no_connect"))
    )
    (net (code "54") (name "unconnected-(U1A-PA7-Pad17)") (class "Default")
      (node (ref "U1") (pin "17") (pinfunction "PA7_17") (pintype "bidirectional+no_connect"))
    )
    (net (code "55") (name "unconnected-(U1A-PA8-Pad29)") (class "Default")
      (node (ref "U1") (pin "29") (pinfunction "PA8_29") (pintype "bidirectional+no_connect"))
    )
    (net (code "56") (name "unconnected-(U1A-PA9-Pad30)") (class "Default")
      (node (ref "U1") (pin "30") (pinfunction "PA9_30") (pintype "passive+no_connect"))
    )
    (net (code "57") (name "unconnected-(U1A-PA10-Pad31)") (class "Default")
      (node (ref "U1") (pin "31") (pinfunction "PA10_31") (pintype "passive+no_connect"))
    )
    (net (code "58") (name "unconnected-(U1A-PA15-Pad38)") (class "Default")
      (node (ref "U1") (pin "38") (pinfunction "PA15_38") (pintype "bidirectional+no_connect"))
    )
    (net (code "59") (name "unconnected-(U1A-PB0-Pad18)") (class "Default")
      (node (ref "U1") (pin "18") (pinfunction "PB0_18") (pintype "bidirectional+no_connect"))
    )
    (net (code "60") (name "unconnected-(U1A-PB1-Pad19)") (class "Default")
      (node (ref "U1") (pin "19") (pinfunction "PB1_19") (pintype "passive+no_connect"))
    )
    (net (code "61") (name "unconnected-(U1A-PB3-Pad39)") (class "Default")
      (node (ref "U1") (pin "39") (pinfunction "PB3_39") (pintype "bidirectional+no_connect"))
    )
    (net (code "62") (name "unconnected-(U1A-PB4-Pad40)") (class "Default")
      (node (ref "U1") (pin "40") (pinfunction "PB4_40") (pintype "bidirectional+no_connect"))
    )
    (net (code "63") (name "unconnected-(U1A-PB5-Pad41)") (class "Default")
      (node (ref "U1") (pin "41") (pinfunction "PB5_41") (pintype "bidirectional+no_connect"))
    )
    (net (code "64") (name "unconnected-(U1A-PB12-Pad25)") (class "Default")
      (node (ref "U1") (pin "25") (pinfunction "PB12_25") (pintype "bidirectional+no_connect"))
    )
    (net (code "65") (name "unconnected-(U1A-PB15-Pad28)") (class "Default")
      (node (ref "U1") (pin "28") (pinfunction "PB15_28") (pintype "bidirectional+no_connect"))
    )
    (net (code "66") (name "unconnected-(U1A-PC13-TAMPER-RTC-Pad2)") (class "Default")
      (node (ref "U1") (pin "2") (pinfunction "PC13-TAMPER-RTC_2") (pintype "bidirectional+no_connect"))
    )
    (net (code "67") (name "unconnected-(U1A-PD0-OSC_IN-Pad5)") (class "Default")
      (node (ref "U1") (pin "5") (pinfunction "PD0-OSC_IN_5") (pintype "bidirectional+no_connect"))
    )
    (net (code "68") (name "unconnected-(U1A-PD1-OSC_OUT-Pad6)") (class "Default")
      (node (ref "U1") (pin "6") (pinfunction "PD1-OSC_OUT_6") (pintype "bidirectional+no_connect"))
    )
    (net (code "69") (name "unconnected-(U4-CS-Pad19)") (class "Default")
      (node (ref "U4") (pin "19") (pinfunction "CS_19") (pintype "output+no_connect"))
    )
  )
)
